# design.net
KiCad netlist of a schematic drawn in Altium Designer
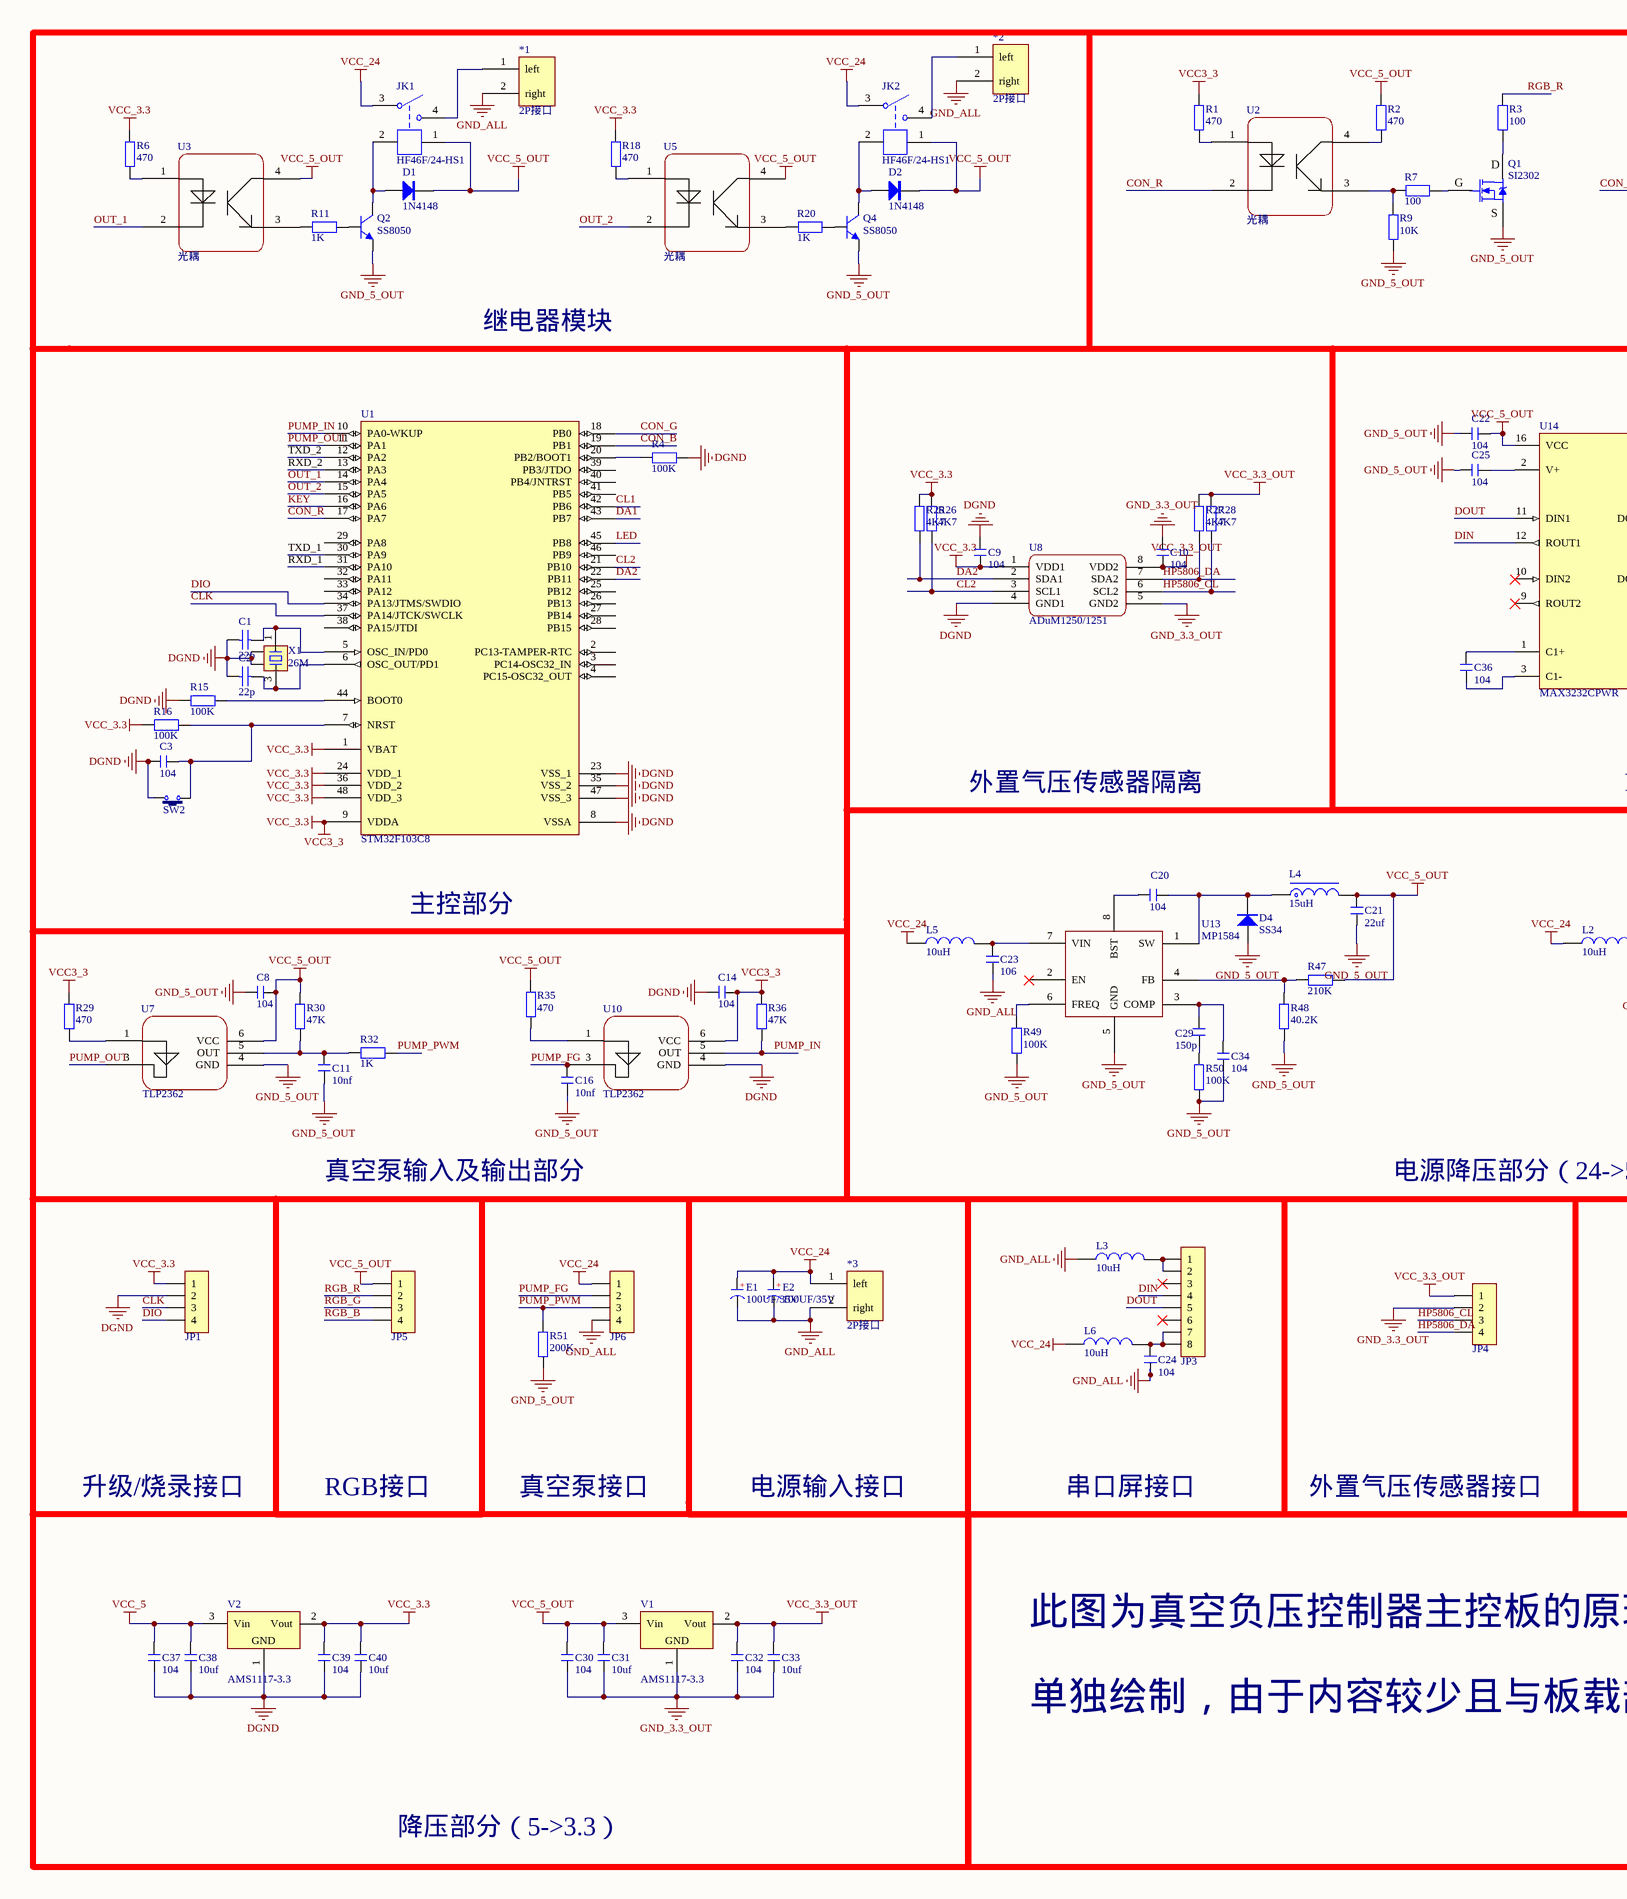
[diagram p0: 气压检测.SchDoc, left]
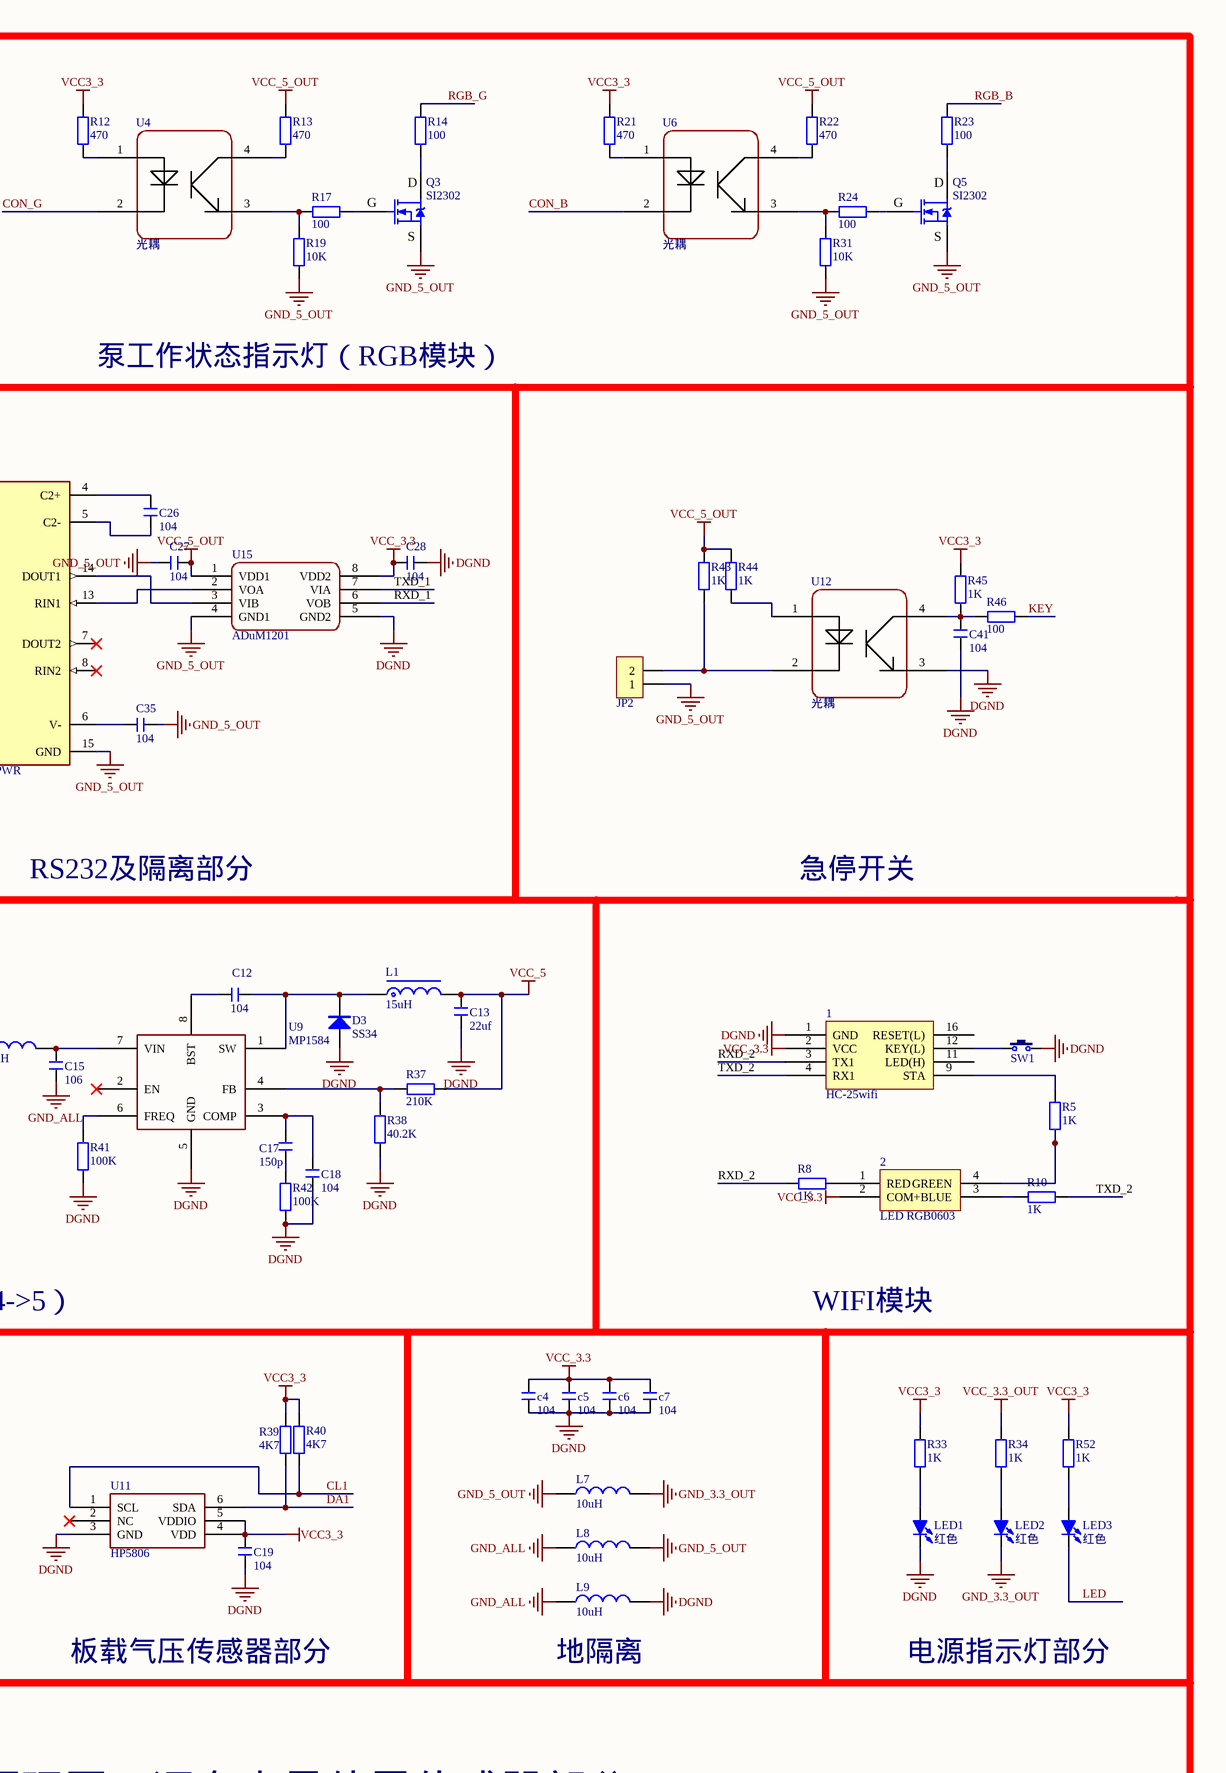
[diagram p1: 气压检测.SchDoc, right]

(export (version "E")
  (design (tool "Eeschema 10.0.6"))
  (components
    (comp (ref "*1") (value "2P接口") (footprint "KF128_2P") (libsource (lib "接口") (part "2P接口")))
    (comp (ref "*2") (value "2P接口") (footprint "KF128_2P") (libsource (lib "接口") (part "2P接口")))
    (comp (ref "*3") (value "2P接口") (footprint "KF128_2P") (libsource (lib "接口") (part "2P接口")))
    (comp (ref "1")
      (value "HC-25wifi")
      (footprint "HC-25")
      (description "HC-25WIFI无线模块")
      (libsource (lib "元件库") (part "HC-25wifi"))
    )
    (comp (ref "2")
      (value "LED RGB0603")
      (footprint "LED RGB 0603")
      (libsource (lib "二极管、LED") (part "LED RGB0603"))
    )
    (comp (ref "C1") (value "22p") (footprint "0603-cap") (libsource (lib "器件库") (part "Cap1")))
    (comp (ref "C2") (value "22p") (footprint "0603-cap") (libsource (lib "器件库") (part "Cap1")))
    (comp (ref "C3")
      (value "104")
      (footprint "C 0603_L")
      (description "无极性贴片电容")
      (fields (field (name "版权归属") "源创客"))
      (libsource (lib "电容、电阻、电感") (part "C"))
    )
    (comp (ref "c4")
      (value "104")
      (footprint "C 0603_L")
      (description "无极性贴片电容")
      (fields (field (name "版权归属") "源创客"))
      (libsource (lib "电容、电阻、电感") (part "C"))
    )
    (comp (ref "c5")
      (value "104")
      (footprint "C 0603_L")
      (description "无极性贴片电容")
      (fields (field (name "版权归属") "源创客"))
      (libsource (lib "电容、电阻、电感") (part "C"))
    )
    (comp (ref "c6")
      (value "104")
      (footprint "C 0603_L")
      (description "无极性贴片电容")
      (fields (field (name "版权归属") "源创客"))
      (libsource (lib "电容、电阻、电感") (part "C"))
    )
    (comp (ref "c7")
      (value "104")
      (footprint "C 0603_L")
      (description "无极性贴片电容")
      (fields (field (name "版权归属") "源创客"))
      (libsource (lib "电容、电阻、电感") (part "C"))
    )
    (comp (ref "C8")
      (value "104")
      (footprint "C 0603_L")
      (description "无极性贴片电容")
      (fields (field (name "版权归属") "源创客"))
      (libsource (lib "电容、电阻、电感") (part "C"))
    )
    (comp (ref "C9")
      (value "104")
      (footprint "C 0603_L")
      (description "无极性贴片电容")
      (fields (field (name "版权归属") "源创客"))
      (libsource (lib "电容、电阻、电感") (part "C"))
    )
    (comp (ref "C10")
      (value "104")
      (footprint "C 0603_L")
      (description "无极性贴片电容")
      (fields (field (name "版权归属") "源创客"))
      (libsource (lib "电容、电阻、电感") (part "C"))
    )
    (comp (ref "C11")
      (value "10nf")
      (footprint "C 0603_L")
      (description "无极性贴片电容")
      (fields (field (name "版权归属") "源创客"))
      (libsource (lib "电容、电阻、电感") (part "C"))
    )
    (comp (ref "C12")
      (value "104")
      (footprint "C 0603_L")
      (description "无极性贴片电容")
      (fields (field (name "版权归属") "源创客"))
      (libsource (lib "电容、电阻、电感") (part "C"))
    )
    (comp (ref "C13")
      (value "22uf")
      (footprint "C 1210_L")
      (description "无极性贴片电容")
      (fields (field (name "版权归属") "源创客"))
      (libsource (lib "电容、电阻、电感") (part "C"))
    )
    (comp (ref "C14")
      (value "104")
      (footprint "C 0603_L")
      (description "无极性贴片电容")
      (fields (field (name "版权归属") "源创客"))
      (libsource (lib "电容、电阻、电感") (part "C"))
    )
    (comp (ref "C15")
      (value "106")
      (footprint "C 1206_L")
      (description "无极性贴片电容")
      (fields (field (name "版权归属") "源创客"))
      (libsource (lib "电容、电阻、电感") (part "C"))
    )
    (comp (ref "C16")
      (value "10nf")
      (footprint "C 0603_L")
      (description "无极性贴片电容")
      (fields (field (name "版权归属") "源创客"))
      (libsource (lib "电容、电阻、电感") (part "C"))
    )
    (comp (ref "C17")
      (value "150p")
      (footprint "C 0603_L")
      (description "无极性贴片电容")
      (fields (field (name "版权归属") "源创客"))
      (libsource (lib "电容、电阻、电感") (part "C"))
    )
    (comp (ref "C18")
      (value "104")
      (footprint "C 0603_L")
      (description "无极性贴片电容")
      (fields (field (name "版权归属") "源创客"))
      (libsource (lib "电容、电阻、电感") (part "C"))
    )
    (comp (ref "C19")
      (value "104")
      (footprint "C 0603_L")
      (description "无极性贴片电容")
      (fields (field (name "版权归属") "源创客"))
      (libsource (lib "电容、电阻、电感") (part "C"))
    )
    (comp (ref "C20")
      (value "104")
      (footprint "C 0603_L")
      (description "无极性贴片电容")
      (fields (field (name "版权归属") "源创客"))
      (libsource (lib "电容、电阻、电感") (part "C"))
    )
    (comp (ref "C21")
      (value "22uf")
      (footprint "C 1210_L")
      (description "无极性贴片电容")
      (fields (field (name "版权归属") "源创客"))
      (libsource (lib "电容、电阻、电感") (part "C"))
    )
    (comp (ref "C22")
      (value "104")
      (footprint "C 0603_L")
      (description "无极性贴片电容")
      (fields (field (name "版权归属") "源创客"))
      (libsource (lib "电容、电阻、电感") (part "C"))
    )
    (comp (ref "C23")
      (value "106")
      (footprint "C 1206_L")
      (description "无极性贴片电容")
      (fields (field (name "版权归属") "源创客"))
      (libsource (lib "电容、电阻、电感") (part "C"))
    )
    (comp (ref "C24")
      (value "104")
      (footprint "C 0603_L")
      (description "无极性贴片电容")
      (fields (field (name "版权归属") "源创客"))
      (libsource (lib "电容、电阻、电感") (part "C"))
    )
    (comp (ref "C25")
      (value "104")
      (footprint "C 0603_L")
      (description "无极性贴片电容")
      (fields (field (name "版权归属") "源创客"))
      (libsource (lib "电容、电阻、电感") (part "C"))
    )
    (comp (ref "C26")
      (value "104")
      (footprint "C 0603_L")
      (description "无极性贴片电容")
      (fields (field (name "版权归属") "源创客"))
      (libsource (lib "电容、电阻、电感") (part "C"))
    )
    (comp (ref "C27")
      (value "104")
      (footprint "C 0603_L")
      (description "无极性贴片电容")
      (fields (field (name "版权归属") "源创客"))
      (libsource (lib "电容、电阻、电感") (part "C"))
    )
    (comp (ref "C28")
      (value "104")
      (footprint "C 0603_L")
      (description "无极性贴片电容")
      (fields (field (name "版权归属") "源创客"))
      (libsource (lib "电容、电阻、电感") (part "C"))
    )
    (comp (ref "C29")
      (value "150p")
      (footprint "C 0603_L")
      (description "无极性贴片电容")
      (fields (field (name "版权归属") "源创客"))
      (libsource (lib "电容、电阻、电感") (part "C"))
    )
    (comp (ref "C30")
      (value "104")
      (footprint "C 0603_L")
      (description "无极性贴片电容")
      (fields (field (name "版权归属") "源创客"))
      (libsource (lib "电容、电阻、电感") (part "C"))
    )
    (comp (ref "C31")
      (value "10uf")
      (footprint "C 0805_L")
      (description "无极性贴片电容")
      (fields (field (name "版权归属") "源创客"))
      (libsource (lib "电容、电阻、电感") (part "C"))
    )
    (comp (ref "C32")
      (value "104")
      (footprint "C 0603_L")
      (description "无极性贴片电容")
      (fields (field (name "版权归属") "源创客"))
      (libsource (lib "电容、电阻、电感") (part "C"))
    )
    (comp (ref "C33")
      (value "10uf")
      (footprint "C 0805_L")
      (description "无极性贴片电容")
      (fields (field (name "版权归属") "源创客"))
      (libsource (lib "电容、电阻、电感") (part "C"))
    )
    (comp (ref "C34")
      (value "104")
      (footprint "C 0603_L")
      (description "无极性贴片电容")
      (fields (field (name "版权归属") "源创客"))
      (libsource (lib "电容、电阻、电感") (part "C"))
    )
    (comp (ref "C35")
      (value "104")
      (footprint "C 0603_L")
      (description "无极性贴片电容")
      (fields (field (name "版权归属") "源创客"))
      (libsource (lib "电容、电阻、电感") (part "C"))
    )
    (comp (ref "C36")
      (value "104")
      (footprint "C 0603_L")
      (description "无极性贴片电容")
      (fields (field (name "版权归属") "源创客"))
      (libsource (lib "电容、电阻、电感") (part "C"))
    )
    (comp (ref "C37")
      (value "104")
      (footprint "C 0603_L")
      (description "无极性贴片电容")
      (fields (field (name "版权归属") "源创客"))
      (libsource (lib "电容、电阻、电感") (part "C"))
    )
    (comp (ref "C38")
      (value "10uf")
      (footprint "C 0805_L")
      (description "无极性贴片电容")
      (fields (field (name "版权归属") "源创客"))
      (libsource (lib "电容、电阻、电感") (part "C"))
    )
    (comp (ref "C39")
      (value "104")
      (footprint "C 0603_L")
      (description "无极性贴片电容")
      (fields (field (name "版权归属") "源创客"))
      (libsource (lib "电容、电阻、电感") (part "C"))
    )
    (comp (ref "C40")
      (value "10uf")
      (footprint "C 0805_L")
      (description "无极性贴片电容")
      (fields (field (name "版权归属") "源创客"))
      (libsource (lib "电容、电阻、电感") (part "C"))
    )
    (comp (ref "C41")
      (value "104")
      (footprint "C 0603_L")
      (description "无极性贴片电容")
      (fields (field (name "版权归属") "源创客"))
      (libsource (lib "电容、电阻、电感") (part "C"))
    )
    (comp (ref "D1")
      (value "1N4148")
      (footprint "SOD-323")
      (description "高速开关二极管")
      (fields (field (name "版权归属") "源创客"))
      (libsource (lib "二极管、LED") (part "1N4148"))
    )
    (comp (ref "D2")
      (value "1N4148")
      (footprint "SOD-323")
      (description "高速开关二极管")
      (fields (field (name "版权归属") "源创客"))
      (libsource (lib "二极管、LED") (part "1N4148"))
    )
    (comp (ref "D3")
      (value "SS34")
      (footprint "SMA")
      (description "肖特基二极管")
      (fields (field (name "版权归属") "源创客"))
      (libsource (lib "二极管、LED") (part "SS210"))
    )
    (comp (ref "D4")
      (value "SS34")
      (footprint "SMA")
      (description "肖特基二极管")
      (fields (field (name "版权归属") "源创客"))
      (libsource (lib "二极管、LED") (part "SS210"))
    )
    (comp (ref "E1")
      (value "100UF/35V")
      (footprint "CAP 3.5*8*11.5")
      (description "直插电解电容")
      (fields (field (name "版权归属") "源创客"))
      (libsource (lib "电容、电阻、电感") (part "C-CAP"))
    )
    (comp (ref "E2")
      (value "100UF/35V")
      (footprint "CAP 3.5*8*11.5")
      (description "直插电解电容")
      (fields (field (name "版权归属") "源创客"))
      (libsource (lib "电容、电阻、电感") (part "C-CAP"))
    )
    (comp (ref "JK1")
      (value "HF46F/24-HS1")
      (footprint "HF46-xx-HS1")
      (description "24V一组常开")
      (fields (field (name "版权归属") "源创客"))
      (libsource (lib "继电器") (part "HF46F/24-HS1"))
    )
    (comp (ref "JK2")
      (value "HF46F/24-HS1")
      (footprint "HF46-xx-HS1")
      (description "24V一组常开")
      (fields (field (name "版权归属") "源创客"))
      (libsource (lib "继电器") (part "HF46F/24-HS1"))
    )
    (comp (ref "JP1")
      (value "HDR-1X4")
      (footprint "XH2.54-LI-4P")
      (description "4P接插件")
      (fields (field (name "版权归属") "源创客"))
      (libsource (lib "排针") (part "Header 4"))
    )
    (comp (ref "JP2")
      (value "HDR-1X2")
      (footprint "XH2.54-LI-2P")
      (description "2P接插件")
      (fields (field (name "版权归属") "源创客"))
      (libsource (lib "排针") (part "Header 2"))
    )
    (comp (ref "JP3")
      (value "HDR-1X8")
      (footprint "FPC2.0-8卧贴-带锁扣")
      (description "8P接插件")
      (fields (field (name "版权归属") "源创客"))
      (libsource (lib "排针") (part "Header 8"))
    )
    (comp (ref "JP4")
      (value "HDR-1X4")
      (footprint "XH2.54-LI-4P")
      (description "4P接插件")
      (fields (field (name "版权归属") "源创客"))
      (libsource (lib "排针") (part "Header 4"))
    )
    (comp (ref "JP5")
      (value "HDR-1X4")
      (footprint "XH2.54-LI-4P")
      (description "4P接插件")
      (fields (field (name "版权归属") "源创客"))
      (libsource (lib "排针") (part "Header 4"))
    )
    (comp (ref "JP6")
      (value "HDR-1X4")
      (footprint "XH2.54-LI-4P")
      (description "4P接插件")
      (fields (field (name "版权归属") "源创客"))
      (libsource (lib "排针") (part "Header 4"))
    )
    (comp (ref "L1")
      (value "15uH")
      (footprint "L 06030")
      (description "贴片功率电感")
      (fields (field (name "版权归属") "源创客"))
      (libsource (lib "电容、电阻、电感") (part "L-CD"))
    )
    (comp (ref "L2")
      (value "10uH")
      (footprint "L 1206")
      (description "小功率贴片电感")
      (fields (field (name "版权归属") "源创客"))
      (libsource (lib "电容、电阻、电感") (part "L"))
    )
    (comp (ref "L3")
      (value "10uH")
      (footprint "L 1206")
      (description "小功率贴片电感")
      (fields (field (name "版权归属") "源创客"))
      (libsource (lib "电容、电阻、电感") (part "L"))
    )
    (comp (ref "L4")
      (value "15uH")
      (footprint "L 06030")
      (description "贴片功率电感")
      (fields (field (name "版权归属") "源创客"))
      (libsource (lib "电容、电阻、电感") (part "L-CD"))
    )
    (comp (ref "L5")
      (value "10uH")
      (footprint "L 1206")
      (description "小功率贴片电感")
      (fields (field (name "版权归属") "源创客"))
      (libsource (lib "电容、电阻、电感") (part "L"))
    )
    (comp (ref "L6")
      (value "10uH")
      (footprint "L 1206")
      (description "小功率贴片电感")
      (fields (field (name "版权归属") "源创客"))
      (libsource (lib "电容、电阻、电感") (part "L"))
    )
    (comp (ref "L7")
      (value "10uH")
      (footprint "L 1206")
      (description "小功率贴片电感")
      (fields (field (name "版权归属") "源创客"))
      (libsource (lib "电容、电阻、电感") (part "L"))
    )
    (comp (ref "L8")
      (value "10uH")
      (footprint "L 1206")
      (description "小功率贴片电感")
      (fields (field (name "版权归属") "源创客"))
      (libsource (lib "电容、电阻、电感") (part "L"))
    )
    (comp (ref "L9")
      (value "10uH")
      (footprint "L 1206")
      (description "小功率贴片电感")
      (fields (field (name "版权归属") "源创客"))
      (libsource (lib "电容、电阻、电感") (part "L"))
    )
    (comp (ref "LED1")
      (value "红色")
      (footprint "LED 0603R")
      (description "贴片LED")
      (fields (field (name "版权归属") "源创客"))
      (libsource (lib "二极管、LED") (part "LED-SMD"))
    )
    (comp (ref "LED2")
      (value "红色")
      (footprint "LED 0603R")
      (description "贴片LED")
      (fields (field (name "版权归属") "源创客"))
      (libsource (lib "二极管、LED") (part "LED-SMD"))
    )
    (comp (ref "LED3")
      (value "红色")
      (footprint "LED 0603R")
      (description "贴片LED")
      (fields (field (name "版权归属") "源创客"))
      (libsource (lib "二极管、LED") (part "LED-SMD"))
    )
    (comp (ref "Q1")
      (value "SI2302")
      (footprint "SOT23-3N")
      (description "N沟道场效应管")
      (fields (field (name "版权归属") "源创客"))
      (libsource (lib "场效应管、可控硅") (part "SI2302"))
    )
    (comp (ref "Q2")
      (value "SS8050")
      (footprint "SOT23-3N")
      (description "高频放大-NPN型")
      (fields (field (name "版权归属") "源创客"))
      (libsource (lib "三极管") (part "8050-SMD"))
    )
    (comp (ref "Q3")
      (value "SI2302")
      (footprint "SOT23-3N")
      (description "N沟道场效应管")
      (fields (field (name "版权归属") "源创客"))
      (libsource (lib "场效应管、可控硅") (part "SI2302"))
    )
    (comp (ref "Q4")
      (value "SS8050")
      (footprint "SOT23-3N")
      (description "高频放大-NPN型")
      (fields (field (name "版权归属") "源创客"))
      (libsource (lib "三极管") (part "8050-SMD"))
    )
    (comp (ref "Q5")
      (value "SI2302")
      (footprint "SOT23-3N")
      (description "N沟道场效应管")
      (fields (field (name "版权归属") "源创客"))
      (libsource (lib "场效应管、可控硅") (part "SI2302"))
    )
    (comp (ref "R1")
      (value "470")
      (footprint "R 0603_L")
      (description "贴片电阻")
      (fields (field (name "版权归属") "源创客"))
      (libsource (lib "电容、电阻、电感") (part "R"))
    )
    (comp (ref "R2")
      (value "470")
      (footprint "R 0603_L")
      (description "贴片电阻")
      (fields (field (name "版权归属") "源创客"))
      (libsource (lib "电容、电阻、电感") (part "R"))
    )
    (comp (ref "R3")
      (value "100")
      (footprint "R 1206_L")
      (description "贴片电阻")
      (fields (field (name "版权归属") "源创客"))
      (libsource (lib "电容、电阻、电感") (part "R"))
    )
    (comp (ref "R4")
      (value "100K")
      (footprint "R 0603_L")
      (description "贴片电阻")
      (fields (field (name "版权归属") "源创客"))
      (libsource (lib "电容、电阻、电感") (part "R"))
    )
    (comp (ref "R5")
      (value "1K")
      (footprint "R 0603_L")
      (description "贴片电阻")
      (fields (field (name "版权归属") "源创客"))
      (libsource (lib "电容、电阻、电感") (part "R"))
    )
    (comp (ref "R6")
      (value "470")
      (footprint "R 0603_L")
      (description "贴片电阻")
      (fields (field (name "版权归属") "源创客"))
      (libsource (lib "电容、电阻、电感") (part "R"))
    )
    (comp (ref "R7")
      (value "100")
      (footprint "R 0603_L")
      (description "贴片电阻")
      (fields (field (name "版权归属") "源创客"))
      (libsource (lib "电容、电阻、电感") (part "R"))
    )
    (comp (ref "R8")
      (value "1K")
      (footprint "R 0603_L")
      (description "贴片电阻")
      (fields (field (name "版权归属") "源创客"))
      (libsource (lib "电容、电阻、电感") (part "R"))
    )
    (comp (ref "R9")
      (value "10K")
      (footprint "R 0603_L")
      (description "贴片电阻")
      (fields (field (name "版权归属") "源创客"))
      (libsource (lib "电容、电阻、电感") (part "R"))
    )
    (comp (ref "R10")
      (value "1K")
      (footprint "R 0603_L")
      (description "贴片电阻")
      (fields (field (name "版权归属") "源创客"))
      (libsource (lib "电容、电阻、电感") (part "R"))
    )
    (comp (ref "R11")
      (value "1K")
      (footprint "R 0603_L")
      (description "贴片电阻")
      (fields (field (name "版权归属") "源创客"))
      (libsource (lib "电容、电阻、电感") (part "R"))
    )
    (comp (ref "R12")
      (value "470")
      (footprint "R 0603_L")
      (description "贴片电阻")
      (fields (field (name "版权归属") "源创客"))
      (libsource (lib "电容、电阻、电感") (part "R"))
    )
    (comp (ref "R13")
      (value "470")
      (footprint "R 0603_L")
      (description "贴片电阻")
      (fields (field (name "版权归属") "源创客"))
      (libsource (lib "电容、电阻、电感") (part "R"))
    )
    (comp (ref "R14")
      (value "100")
      (footprint "R 1206_L")
      (description "贴片电阻")
      (fields (field (name "版权归属") "源创客"))
      (libsource (lib "电容、电阻、电感") (part "R"))
    )
    (comp (ref "R15")
      (value "100K")
      (footprint "R 0603_L")
      (description "贴片电阻")
      (fields (field (name "版权归属") "源创客"))
      (libsource (lib "电容、电阻、电感") (part "R"))
    )
    (comp (ref "R16")
      (value "100K")
      (footprint "R 0603_L")
      (description "贴片电阻")
      (fields (field (name "版权归属") "源创客"))
      (libsource (lib "电容、电阻、电感") (part "R"))
    )
    (comp (ref "R17")
      (value "100")
      (footprint "R 0603_L")
      (description "贴片电阻")
      (fields (field (name "版权归属") "源创客"))
      (libsource (lib "电容、电阻、电感") (part "R"))
    )
    (comp (ref "R18")
      (value "470")
      (footprint "R 0603_L")
      (description "贴片电阻")
      (fields (field (name "版权归属") "源创客"))
      (libsource (lib "电容、电阻、电感") (part "R"))
    )
    (comp (ref "R19")
      (value "10K")
      (footprint "R 0603_L")
      (description "贴片电阻")
      (fields (field (name "版权归属") "源创客"))
      (libsource (lib "电容、电阻、电感") (part "R"))
    )
    (comp (ref "R20")
      (value "1K")
      (footprint "R 0603_L")
      (description "贴片电阻")
      (fields (field (name "版权归属") "源创客"))
      (libsource (lib "电容、电阻、电感") (part "R"))
    )
    (comp (ref "R21")
      (value "470")
      (footprint "R 0603_L")
      (description "贴片电阻")
      (fields (field (name "版权归属") "源创客"))
      (libsource (lib "电容、电阻、电感") (part "R"))
    )
    (comp (ref "R22")
      (value "470")
      (footprint "R 0603_L")
      (description "贴片电阻")
      (fields (field (name "版权归属") "源创客"))
      (libsource (lib "电容、电阻、电感") (part "R"))
    )
    (comp (ref "R23")
      (value "100")
      (footprint "R 1206_L")
      (description "贴片电阻")
      (fields (field (name "版权归属") "源创客"))
      (libsource (lib "电容、电阻、电感") (part "R"))
    )
    (comp (ref "R24")
      (value "100")
      (footprint "R 0603_L")
      (description "贴片电阻")
      (fields (field (name "版权归属") "源创客"))
      (libsource (lib "电容、电阻、电感") (part "R"))
    )
    (comp (ref "R25")
      (value "4K7")
      (footprint "R 0603_L")
      (description "贴片电阻")
      (fields (field (name "版权归属") "源创客"))
      (libsource (lib "电容、电阻、电感") (part "R"))
    )
    (comp (ref "R26")
      (value "4K7")
      (footprint "R 0603_L")
      (description "贴片电阻")
      (fields (field (name "版权归属") "源创客"))
      (libsource (lib "电容、电阻、电感") (part "R"))
    )
    (comp (ref "R27")
      (value "4K7")
      (footprint "R 0603_L")
      (description "贴片电阻")
      (fields (field (name "版权归属") "源创客"))
      (libsource (lib "电容、电阻、电感") (part "R"))
    )
    (comp (ref "R28")
      (value "4K7")
      (footprint "R 0603_L")
      (description "贴片电阻")
      (fields (field (name "版权归属") "源创客"))
      (libsource (lib "电容、电阻、电感") (part "R"))
    )
    (comp (ref "R29")
      (value "470")
      (footprint "R 0603_L")
      (description "贴片电阻")
      (fields (field (name "版权归属") "源创客"))
      (libsource (lib "电容、电阻、电感") (part "R"))
    )
    (comp (ref "R30")
      (value "47K")
      (footprint "R 0603_L")
      (description "贴片电阻")
      (fields (field (name "版权归属") "源创客"))
      (libsource (lib "电容、电阻、电感") (part "R"))
    )
    (comp (ref "R31")
      (value "10K")
      (footprint "R 0603_L")
      (description "贴片电阻")
      (fields (field (name "版权归属") "源创客"))
      (libsource (lib "电容、电阻、电感") (part "R"))
    )
    (comp (ref "R32")
      (value "1K")
      (footprint "R 0603_L")
      (description "贴片电阻")
      (fields (field (name "版权归属") "源创客"))
      (libsource (lib "电容、电阻、电感") (part "R"))
    )
    (comp (ref "R33")
      (value "1K")
      (footprint "R 0603_L")
      (description "贴片电阻")
      (fields (field (name "版权归属") "源创客"))
      (libsource (lib "电容、电阻、电感") (part "R"))
    )
    (comp (ref "R34")
      (value "1K")
      (footprint "R 0603_L")
      (description "贴片电阻")
      (fields (field (name "版权归属") "源创客"))
      (libsource (lib "电容、电阻、电感") (part "R"))
    )
    (comp (ref "R35")
      (value "470")
      (footprint "R 0603_L")
      (description "贴片电阻")
      (fields (field (name "版权归属") "源创客"))
      (libsource (lib "电容、电阻、电感") (part "R"))
    )
    (comp (ref "R36")
      (value "47K")
      (footprint "R 0603_L")
      (description "贴片电阻")
      (fields (field (name "版权归属") "源创客"))
      (libsource (lib "电容、电阻、电感") (part "R"))
    )
    (comp (ref "R37")
      (value "210K")
      (footprint "R 0603_L")
      (description "贴片电阻")
      (fields (field (name "版权归属") "源创客"))
      (libsource (lib "电容、电阻、电感") (part "R"))
    )
    (comp (ref "R38")
      (value "40.2K")
      (footprint "R 0603_L")
      (description "贴片电阻")
      (fields (field (name "版权归属") "源创客"))
      (libsource (lib "电容、电阻、电感") (part "R"))
    )
    (comp (ref "R39")
      (value "4K7")
      (footprint "R 0603_L")
      (description "贴片电阻")
      (fields (field (name "版权归属") "源创客"))
      (libsource (lib "电容、电阻、电感") (part "R"))
    )
    (comp (ref "R40")
      (value "4K7")
      (footprint "R 0603_L")
      (description "贴片电阻")
      (fields (field (name "版权归属") "源创客"))
      (libsource (lib "电容、电阻、电感") (part "R"))
    )
    (comp (ref "R41")
      (value "100K")
      (footprint "R 0603_L")
      (description "贴片电阻")
      (fields (field (name "版权归属") "源创客"))
      (libsource (lib "电容、电阻、电感") (part "R"))
    )
    (comp (ref "R42")
      (value "100K")
      (footprint "R 0603_L")
      (description "贴片电阻")
      (fields (field (name "版权归属") "源创客"))
      (libsource (lib "电容、电阻、电感") (part "R"))
    )
    (comp (ref "R43")
      (value "1K")
      (footprint "R 0603_L")
      (description "贴片电阻")
      (fields (field (name "版权归属") "源创客"))
      (libsource (lib "电容、电阻、电感") (part "R"))
    )
    (comp (ref "R44")
      (value "1K")
      (footprint "R 0603_L")
      (description "贴片电阻")
      (fields (field (name "版权归属") "源创客"))
      (libsource (lib "电容、电阻、电感") (part "R"))
    )
    (comp (ref "R45")
      (value "1K")
      (footprint "R 0603_L")
      (description "贴片电阻")
      (fields (field (name "版权归属") "源创客"))
      (libsource (lib "电容、电阻、电感") (part "R"))
    )
    (comp (ref "R46")
      (value "100")
      (footprint "R 0603_L")
      (description "贴片电阻")
      (fields (field (name "版权归属") "源创客"))
      (libsource (lib "电容、电阻、电感") (part "R"))
    )
    (comp (ref "R47")
      (value "210K")
      (footprint "R 0603_L")
      (description "贴片电阻")
      (fields (field (name "版权归属") "源创客"))
      (libsource (lib "电容、电阻、电感") (part "R"))
    )
    (comp (ref "R48")
      (value "40.2K")
      (footprint "R 0603_L")
      (description "贴片电阻")
      (fields (field (name "版权归属") "源创客"))
      (libsource (lib "电容、电阻、电感") (part "R"))
    )
    (comp (ref "R49")
      (value "100K")
      (footprint "R 0603_L")
      (description "贴片电阻")
      (fields (field (name "版权归属") "源创客"))
      (libsource (lib "电容、电阻、电感") (part "R"))
    )
    (comp (ref "R50")
      (value "100K")
      (footprint "R 0603_L")
      (description "贴片电阻")
      (fields (field (name "版权归属") "源创客"))
      (libsource (lib "电容、电阻、电感") (part "R"))
    )
    (comp (ref "R51")
      (value "200K")
      (footprint "R 0603_L")
      (description "贴片电阻")
      (fields (field (name "版权归属") "源创客"))
      (libsource (lib "电容、电阻、电感") (part "R"))
    )
    (comp (ref "R52")
      (value "1K")
      (footprint "R 0603_L")
      (description "贴片电阻")
      (fields (field (name "版权归属") "源创客"))
      (libsource (lib "电容、电阻、电感") (part "R"))
    )
    (comp (ref "SW1")
      (value "3x6x5")
      (footprint "TSW SMD-3*4*2")
      (description "3x6轻触开关")
      (fields (field (name "版权归属") "源创客"))
      (libsource (lib "") (part "TSW 3x6_1"))
    )
    (comp (ref "SW2")
      (value "3x6x5")
      (footprint "TSW SMD-3*4*2")
      (description "3x6轻触开关")
      (fields (field (name "版权归属") "源创客"))
      (libsource (lib "开关、按键") (part "TSW 3x6"))
    )
    (comp (ref "U1")
      (value "STM32F103C8")
      (footprint "LQFP48 7X7_N")
      (description "Flaah:64/RAM:20/IO:36")
      (fields (field (name "版权归属") "源创客"))
      (libsource (lib "STM32系列") (part "STM32F103C8"))
    )
    (comp (ref "U2")
      (value "光耦")
      (footprint "SMD-4")
      (description "低速单通道普通光耦")
      (libsource (lib "元件库") (part "光耦"))
    )
    (comp (ref "U3")
      (value "光耦")
      (footprint "SMD-4")
      (description "低速单通道普通光耦")
      (libsource (lib "元件库") (part "光耦"))
    )
    (comp (ref "U4")
      (value "光耦")
      (footprint "SMD-4")
      (description "低速单通道普通光耦")
      (libsource (lib "元件库") (part "光耦"))
    )
    (comp (ref "U5")
      (value "光耦")
      (footprint "SMD-4")
      (description "低速单通道普通光耦")
      (libsource (lib "元件库") (part "光耦"))
    )
    (comp (ref "U6")
      (value "光耦")
      (footprint "SMD-4")
      (description "低速单通道普通光耦")
      (libsource (lib "元件库") (part "光耦"))
    )
    (comp (ref "U7")
      (value "TLP2362")
      (footprint "SO6")
      (description "高速光耦（TOSHIBA)2.7-5.5V")
      (libsource (lib "元件库") (part "TLP2362"))
    )
    (comp (ref "U8")
      (value "ADuM1250/1251")
      (footprint "SOP8_L")
      (libsource (lib "芯片库") (part "ADuM1250/1251"))
    )
    (comp (ref "U9")
      (value "MP1584")
      (footprint "SOP8_N")
      (description "DC降压芯片")
      (libsource (lib "芯片库") (part "MP1584"))
    )
    (comp (ref "U10")
      (value "TLP2362")
      (footprint "SO6")
      (description "高速光耦（TOSHIBA)2.7-5.5V")
      (libsource (lib "元件库") (part "TLP2362"))
    )
    (comp (ref "U11")
      (value "HP5806")
      (footprint "HP5806")
      (description "I2C气压传感器")
      (libsource (lib "元件库") (part "HP5806"))
    )
    (comp (ref "U12")
      (value "光耦")
      (footprint "SMD-4")
      (description "低速单通道普通光耦")
      (libsource (lib "元件库") (part "光耦"))
    )
    (comp (ref "U13")
      (value "MP1584")
      (footprint "SOP8_N")
      (description "DC降压芯片")
      (libsource (lib "芯片库") (part "MP1584"))
    )
    (comp (ref "U14")
      (value "MAX3232CPWR")
      (footprint "FP-PW0016A-IPC_B")
      (description "IC TRANSCEIVER FULL 2/2 16TSSOP")
      (libsource (lib "Altium Content Vault") (part "35df3863a87d4fc5d5ee2311e0e958c"))
    )
    (comp (ref "U15")
      (value "ADuM1201")
      (footprint "SOP8_N")
      (description "通用隔离芯片")
      (libsource (lib "芯片库") (part "ADuM1201"))
    )
    (comp (ref "V1")
      (value "AMS1117-3.3")
      (footprint "SOT223_N")
      (description "三端稳压芯片")
      (fields (field (name "版权归属") "源创客"))
      (libsource (lib "电源类芯片") (part "AMS1117"))
    )
    (comp (ref "V2")
      (value "AMS1117-3.3")
      (footprint "SOT223_N")
      (description "三端稳压芯片")
      (fields (field (name "版权归属") "源创客"))
      (libsource (lib "电源类芯片") (part "AMS1117"))
    )
    (comp (ref "X1")
      (value "26M")
      (footprint "OSC 3225-4P")
      (description "4脚无源晶振")
      (fields (field (name "版权归属") "源创客"))
      (libsource (lib "晶振、保险丝") (part "XTAL-4P"))
    )
  )
  (nets
    (net (code "1") (name "/CL1") (class "Default")
      (node (ref "R40") (pin "2") (pinfunction "2_2") (pintype "passive"))
      (node (ref "U1") (pin "42") (pinfunction "PB6_42") (pintype "bidirectional"))
      (node (ref "U11") (pin "1") (pinfunction "SCL_1") (pintype "passive"))
    )
    (net (code "2") (name "/CL2") (class "Default")
      (node (ref "R26") (pin "1") (pinfunction "1_1") (pintype "passive"))
      (node (ref "U1") (pin "21") (pinfunction "PB10_21") (pintype "bidirectional"))
      (node (ref "U8") (pin "3") (pinfunction "SCL1_3") (pintype "passive"))
    )
    (net (code "3") (name "/CLK") (class "Default")
      (node (ref "JP1") (pin "3") (pinfunction "3_3") (pintype "passive"))
      (node (ref "U1") (pin "37") (pinfunction "PA14/JTCK/SWCLK_37") (pintype "bidirectional"))
    )
    (net (code "4") (name "/CON_B") (class "Default")
      (node (ref "U1") (pin "19") (pinfunction "PB1_19") (pintype "bidirectional"))
      (node (ref "U6") (pin "2") (pintype "passive"))
    )
    (net (code "5") (name "/CON_G") (class "Default")
      (node (ref "U1") (pin "18") (pinfunction "PB0_18") (pintype "bidirectional"))
      (node (ref "U4") (pin "2") (pintype "passive"))
    )
    (net (code "6") (name "/CON_R") (class "Default")
      (node (ref "U1") (pin "17") (pinfunction "PA7_17") (pintype "bidirectional"))
      (node (ref "U2") (pin "2") (pintype "passive"))
    )
    (net (code "7") (name "/DA1") (class "Default")
      (node (ref "R39") (pin "2") (pinfunction "2_2") (pintype "passive"))
      (node (ref "U1") (pin "43") (pinfunction "PB7_43") (pintype "bidirectional"))
      (node (ref "U11") (pin "6") (pinfunction "SDA_6") (pintype "passive"))
    )
    (net (code "8") (name "/DA2") (class "Default")
      (node (ref "R25") (pin "1") (pinfunction "1_1") (pintype "passive"))
      (node (ref "U1") (pin "22") (pinfunction "PB11_22") (pintype "bidirectional"))
      (node (ref "U8") (pin "2") (pinfunction "SDA1_2") (pintype "passive"))
    )
    (net (code "9") (name "/DIN") (class "Default")
      (node (ref "JP3") (pin "4") (pinfunction "4_4") (pintype "passive"))
      (node (ref "U14") (pin "12") (pinfunction "ROUT1_12") (pintype "output"))
    )
    (net (code "10") (name "/DIO") (class "Default")
      (node (ref "JP1") (pin "4") (pinfunction "4_4") (pintype "passive"))
      (node (ref "U1") (pin "34") (pinfunction "PA13/JTMS/SWDIO_34") (pintype "bidirectional"))
    )
    (net (code "11") (name "/DOUT") (class "Default")
      (node (ref "JP3") (pin "5") (pinfunction "5_5") (pintype "passive"))
      (node (ref "U14") (pin "11") (pinfunction "DIN1_11") (pintype "input"))
    )
    (net (code "12") (name "/HP5806_CL") (class "Default")
      (node (ref "JP4") (pin "3") (pinfunction "3_3") (pintype "passive"))
      (node (ref "R28") (pin "1") (pinfunction "1_1") (pintype "passive"))
      (node (ref "U8") (pin "6") (pinfunction "SCL2_6") (pintype "passive"))
    )
    (net (code "13") (name "/HP5806_DA") (class "Default")
      (node (ref "JP4") (pin "4") (pinfunction "4_4") (pintype "passive"))
      (node (ref "R27") (pin "1") (pinfunction "1_1") (pintype "passive"))
      (node (ref "U8") (pin "7") (pinfunction "SDA2_7") (pintype "passive"))
    )
    (net (code "14") (name "/KEY") (class "Default")
      (node (ref "R46") (pin "1") (pinfunction "1_1") (pintype "passive"))
      (node (ref "U1") (pin "16") (pinfunction "PA6_16") (pintype "bidirectional"))
    )
    (net (code "15") (name "/LED") (class "Default")
      (node (ref "LED3") (pin "2") (pinfunction "K_2") (pintype "passive"))
      (node (ref "U1") (pin "45") (pinfunction "PB8_45") (pintype "bidirectional"))
    )
    (net (code "16") (name "/OUT_1") (class "Default")
      (node (ref "U1") (pin "14") (pinfunction "PA4_14") (pintype "bidirectional"))
      (node (ref "U3") (pin "2") (pintype "passive"))
    )
    (net (code "17") (name "/OUT_2") (class "Default")
      (node (ref "U1") (pin "15") (pinfunction "PA5_15") (pintype "bidirectional"))
      (node (ref "U5") (pin "2") (pintype "passive"))
    )
    (net (code "18") (name "/PUMP_FG") (class "Default")
      (node (ref "C16") (pin "1") (pinfunction "1_1") (pintype "passive"))
      (node (ref "JP6") (pin "2") (pinfunction "2_2") (pintype "passive"))
      (node (ref "U10") (pin "3") (pintype "passive"))
    )
    (net (code "19") (name "/PUMP_IN") (class "Default")
      (node (ref "R36") (pin "1") (pinfunction "1_1") (pintype "passive"))
      (node (ref "U1") (pin "10") (pinfunction "PA0-WKUP_10") (pintype "bidirectional"))
      (node (ref "U10") (pin "5") (pinfunction "OUT_5") (pintype "passive"))
    )
    (net (code "20") (name "/PUMP_OUT") (class "Default")
      (node (ref "U1") (pin "11") (pinfunction "PA1_11") (pintype "bidirectional"))
      (node (ref "U7") (pin "3") (pintype "passive"))
    )
    (net (code "21") (name "/PUMP_PWM") (class "Default")
      (node (ref "JP6") (pin "3") (pinfunction "3_3") (pintype "passive"))
      (node (ref "R32") (pin "1") (pinfunction "1_1") (pintype "passive"))
      (node (ref "R51") (pin "2") (pinfunction "2_2") (pintype "passive"))
    )
    (net (code "22") (name "/RGB_B") (class "Default")
      (node (ref "JP5") (pin "4") (pinfunction "4_4") (pintype "passive"))
      (node (ref "R23") (pin "2") (pinfunction "2_2") (pintype "passive"))
    )
    (net (code "23") (name "/RGB_G") (class "Default")
      (node (ref "JP5") (pin "3") (pinfunction "3_3") (pintype "passive"))
      (node (ref "R14") (pin "2") (pinfunction "2_2") (pintype "passive"))
    )
    (net (code "24") (name "/RGB_R") (class "Default")
      (node (ref "JP5") (pin "2") (pinfunction "2_2") (pintype "passive"))
      (node (ref "R3") (pin "2") (pinfunction "2_2") (pintype "passive"))
    )
    (net (code "25") (name "/RXD_1") (class "Default")
      (node (ref "U1") (pin "31") (pinfunction "PA10_31") (pintype "bidirectional"))
      (node (ref "U15") (pin "6") (pinfunction "VOB_6") (pintype "passive"))
    )
    (net (code "26") (name "/RXD_2") (class "Default")
      (node (ref "1") (pin "3") (pinfunction "TX1_3") (pintype "passive"))
      (node (ref "R8") (pin "1") (pinfunction "1_1") (pintype "passive"))
      (node (ref "U1") (pin "13") (pinfunction "PA3_13") (pintype "bidirectional"))
    )
    (net (code "27") (name "/TXD_1") (class "Default")
      (node (ref "U1") (pin "30") (pinfunction "PA9_30") (pintype "bidirectional"))
      (node (ref "U15") (pin "7") (pinfunction "VIA_7") (pintype "passive"))
    )
    (net (code "28") (name "/TXD_2") (class "Default")
      (node (ref "1") (pin "4") (pinfunction "RX1_4") (pintype "passive"))
      (node (ref "R10") (pin "2") (pinfunction "2_2") (pintype "passive"))
      (node (ref "U1") (pin "12") (pinfunction "PA2_12") (pintype "bidirectional"))
    )
    (net (code "29") (name "DGND") (class "Default")
      (node (ref "1") (pin "1") (pinfunction "GND_1") (pintype "passive"))
      (node (ref "C1") (pin "2") (pinfunction "2_2") (pintype "passive"))
      (node (ref "C13") (pin "1") (pinfunction "1_1") (pintype "passive"))
      (node (ref "C14") (pin "2") (pinfunction "2_2") (pintype "passive"))
      (node (ref "C18") (pin "1") (pinfunction "1_1") (pintype "passive"))
      (node (ref "C19") (pin "2") (pinfunction "2_2") (pintype "passive"))
      (node (ref "C2") (pin "2") (pinfunction "2_2") (pintype "passive"))
      (node (ref "C28") (pin "2") (pinfunction "2_2") (pintype "passive"))
      (node (ref "C3") (pin "1") (pinfunction "1_1") (pintype "passive"))
      (node (ref "C37") (pin "1") (pinfunction "1_1") (pintype "passive"))
      (node (ref "C38") (pin "1") (pinfunction "1_1") (pintype "passive"))
      (node (ref "C39") (pin "1") (pinfunction "1_1") (pintype "passive"))
      (node (ref "C40") (pin "1") (pinfunction "1_1") (pintype "passive"))
      (node (ref "C41") (pin "2") (pinfunction "2_2") (pintype "passive"))
      (node (ref "C9") (pin "2") (pinfunction "2_2") (pintype "passive"))
      (node (ref "D3") (pin "1") (pinfunction "A_1") (pintype "passive"))
      (node (ref "JP1") (pin "2") (pinfunction "2_2") (pintype "passive"))
      (node (ref "L9") (pin "2") (pinfunction "2_2") (pintype "passive"))
      (node (ref "LED1") (pin "2") (pinfunction "K_2") (pintype "passive"))
      (node (ref "R15") (pin "1") (pinfunction "1_1") (pintype "passive"))
      (node (ref "R38") (pin "2") (pinfunction "2_2") (pintype "passive"))
      (node (ref "R4") (pin "1") (pinfunction "1_1") (pintype "passive"))
      (node (ref "R41") (pin "1") (pinfunction "1_1") (pintype "passive"))
      (node (ref "R42") (pin "2") (pinfunction "2_2") (pintype "passive"))
      (node (ref "SW1") (pin "2") (pinfunction "2_2") (pintype "passive"))
      (node (ref "SW2") (pin "2") (pinfunction "2_2") (pintype "passive"))
      (node (ref "U1") (pin "23") (pinfunction "VSS_1_23") (pintype "power_in"))
      (node (ref "U1") (pin "35") (pinfunction "VSS_2_35") (pintype "power_in"))
      (node (ref "U1") (pin "47") (pinfunction "VSS_3_47") (pintype "power_in"))
      (node (ref "U1") (pin "8") (pinfunction "VSSA_8") (pintype "power_in"))
      (node (ref "U10") (pin "4") (pinfunction "GND_4") (pintype "passive"))
      (node (ref "U11") (pin "3") (pinfunction "GND_3") (pintype "passive"))
      (node (ref "U12") (pin "3") (pintype "passive"))
      (node (ref "U15") (pin "5") (pinfunction "GND2_5") (pintype "passive"))
      (node (ref "U8") (pin "4") (pinfunction "GND1_4") (pintype "passive"))
      (node (ref "U9") (pin "5") (pinfunction "GND_5") (pintype "passive"))
      (node (ref "V2") (pin "1") (pinfunction "GND_1") (pintype "passive"))
      (node (ref "X1") (pin "2") (pinfunction "2_2") (pintype "passive"))
      (node (ref "X1") (pin "4") (pinfunction "4_4") (pintype "passive"))
      (node (ref "c4") (pin "1") (pinfunction "1_1") (pintype "passive"))
      (node (ref "c5") (pin "1") (pinfunction "1_1") (pintype "passive"))
      (node (ref "c6") (pin "1") (pinfunction "1_1") (pintype "passive"))
      (node (ref "c7") (pin "1") (pinfunction "1_1") (pintype "passive"))
    )
    (net (code "30") (name "GND_3.3_OUT") (class "Default")
      (node (ref "C10") (pin "2") (pinfunction "2_2") (pintype "passive"))
      (node (ref "C30") (pin "1") (pinfunction "1_1") (pintype "passive"))
      (node (ref "C31") (pin "1") (pinfunction "1_1") (pintype "passive"))
      (node (ref "C32") (pin "1") (pinfunction "1_1") (pintype "passive"))
      (node (ref "C33") (pin "1") (pinfunction "1_1") (pintype "passive"))
      (node (ref "JP4") (pin "2") (pinfunction "2_2") (pintype "passive"))
      (node (ref "L7") (pin "2") (pinfunction "2_2") (pintype "passive"))
      (node (ref "LED2") (pin "2") (pinfunction "K_2") (pintype "passive"))
      (node (ref "U8") (pin "5") (pinfunction "GND2_5") (pintype "passive"))
      (node (ref "V1") (pin "1") (pinfunction "GND_1") (pintype "passive"))
    )
    (net (code "31") (name "GND_5_OUT") (class "Default")
      (node (ref "C11") (pin "2") (pinfunction "2_2") (pintype "passive"))
      (node (ref "C16") (pin "2") (pinfunction "2_2") (pintype "passive"))
      (node (ref "C21") (pin "1") (pinfunction "1_1") (pintype "passive"))
      (node (ref "C22") (pin "2") (pinfunction "2_2") (pintype "passive"))
      (node (ref "C25") (pin "2") (pinfunction "2_2") (pintype "passive"))
      (node (ref "C27") (pin "2") (pinfunction "2_2") (pintype "passive"))
      (node (ref "C34") (pin "1") (pinfunction "1_1") (pintype "passive"))
      (node (ref "C35") (pin "2") (pinfunction "2_2") (pintype "passive"))
      (node (ref "C8") (pin "2") (pinfunction "2_2") (pintype "passive"))
      (node (ref "D4") (pin "1") (pinfunction "A_1") (pintype "passive"))
      (node (ref "JP2") (pin "1") (pinfunction "1_1") (pintype "passive"))
      (node (ref "L7") (pin "1") (pinfunction "1_1") (pintype "passive"))
      (node (ref "L8") (pin "2") (pinfunction "2_2") (pintype "passive"))
      (node (ref "Q1") (pin "2") (pinfunction "S_2") (pintype "passive"))
      (node (ref "Q2") (pin "2") (pinfunction "E_2") (pintype "passive"))
      (node (ref "Q3") (pin "2") (pinfunction "S_2") (pintype "passive"))
      (node (ref "Q4") (pin "2") (pinfunction "E_2") (pintype "passive"))
      (node (ref "Q5") (pin "2") (pinfunction "S_2") (pintype "passive"))
      (node (ref "R19") (pin "1") (pinfunction "1_1") (pintype "passive"))
      (node (ref "R31") (pin "1") (pinfunction "1_1") (pintype "passive"))
      (node (ref "R48") (pin "2") (pinfunction "2_2") (pintype "passive"))
      (node (ref "R49") (pin "1") (pinfunction "1_1") (pintype "passive"))
      (node (ref "R50") (pin "2") (pinfunction "2_2") (pintype "passive"))
      (node (ref "R51") (pin "1") (pinfunction "1_1") (pintype "passive"))
      (node (ref "R9") (pin "1") (pinfunction "1_1") (pintype "passive"))
      (node (ref "U13") (pin "5") (pinfunction "GND_5") (pintype "passive"))
      (node (ref "U14") (pin "15") (pinfunction "GND_15") (pintype "power_in"))
      (node (ref "U15") (pin "4") (pinfunction "GND1_4") (pintype "passive"))
      (node (ref "U7") (pin "4") (pinfunction "GND_4") (pintype "passive"))
    )
    (net (code "32") (name "GND_ALL") (class "Default")
      (node (ref "*1") (pin "2") (pinfunction "right_2") (pintype "passive"))
      (node (ref "*2") (pin "2") (pinfunction "right_2") (pintype "passive"))
      (node (ref "*3") (pin "2") (pinfunction "right_2") (pintype "passive"))
      (node (ref "C15") (pin "1") (pinfunction "1_1") (pintype "passive"))
      (node (ref "C23") (pin "1") (pinfunction "1_1") (pintype "passive"))
      (node (ref "C24") (pin "2") (pinfunction "2_2") (pintype "passive"))
      (node (ref "E1") (pin "2") (pinfunction "K_2") (pintype "passive"))
      (node (ref "E2") (pin "2") (pinfunction "K_2") (pintype "passive"))
      (node (ref "JP6") (pin "4") (pinfunction "4_4") (pintype "passive"))
      (node (ref "L3") (pin "1") (pinfunction "1_1") (pintype "passive"))
      (node (ref "L8") (pin "1") (pinfunction "1_1") (pintype "passive"))
      (node (ref "L9") (pin "1") (pinfunction "1_1") (pintype "passive"))
    )
    (net (code "33") (name "Net-(*1-left)") (class "Default")
      (node (ref "*1") (pin "1") (pinfunction "left_1") (pintype "passive"))
      (node (ref "JK1") (pin "4") (pinfunction "4_4") (pintype "passive"))
    )
    (net (code "34") (name "Net-(*2-left)") (class "Default")
      (node (ref "*2") (pin "1") (pinfunction "left_1") (pintype "passive"))
      (node (ref "JK2") (pin "4") (pinfunction "4_4") (pintype "passive"))
    )
    (net (code "35") (name "Net-(1-KEY(L))") (class "Default")
      (node (ref "1") (pin "12") (pinfunction "KEY(L)_12") (pintype "passive"))
      (node (ref "SW1") (pin "1") (pinfunction "1_1") (pintype "passive"))
    )
    (net (code "36") (name "Net-(1-STA)") (class "Default")
      (node (ref "1") (pin "9") (pinfunction "STA_9") (pintype "passive"))
      (node (ref "R5") (pin "1") (pinfunction "1_1") (pintype "passive"))
    )
    (net (code "37") (name "Net-(2-BLUE)") (class "Default")
      (node (ref "2") (pin "3") (pinfunction "BLUE_3") (pintype "passive"))
      (node (ref "R10") (pin "1") (pinfunction "1_1") (pintype "passive"))
    )
    (net (code "38") (name "Net-(2-GREEN)") (class "Default")
      (node (ref "2") (pin "4") (pinfunction "GREEN_4") (pintype "passive"))
      (node (ref "R5") (pin "2") (pinfunction "2_2") (pintype "passive"))
    )
    (net (code "39") (name "Net-(2-RED)") (class "Default")
      (node (ref "2") (pin "1") (pinfunction "RED_1") (pintype "passive"))
      (node (ref "R8") (pin "2") (pinfunction "2_2") (pintype "passive"))
    )
    (net (code "40") (name "Net-(C17-Pad1)") (class "Default")
      (node (ref "C17") (pin "1") (pinfunction "1_1") (pintype "passive"))
      (node (ref "R42") (pin "1") (pinfunction "1_1") (pintype "passive"))
    )
    (net (code "41") (name "Net-(C24-Pad1)") (class "Default")
      (node (ref "C24") (pin "1") (pinfunction "1_1") (pintype "passive"))
      (node (ref "JP3") (pin "7") (pinfunction "7_7") (pintype "passive"))
      (node (ref "JP3") (pin "8") (pinfunction "8_8") (pintype "passive"))
      (node (ref "L6") (pin "2") (pinfunction "2_2") (pintype "passive"))
    )
    (net (code "42") (name "Net-(C29-Pad1)") (class "Default")
      (node (ref "C29") (pin "1") (pinfunction "1_1") (pintype "passive"))
      (node (ref "R50") (pin "1") (pinfunction "1_1") (pintype "passive"))
    )
    (net (code "43") (name "Net-(C41-Pad1)") (class "Default")
      (node (ref "C41") (pin "1") (pinfunction "1_1") (pintype "passive"))
      (node (ref "R45") (pin "1") (pinfunction "1_1") (pintype "passive"))
      (node (ref "R46") (pin "2") (pinfunction "2_2") (pintype "passive"))
      (node (ref "U12") (pin "4") (pintype "passive"))
    )
    (net (code "44") (name "Net-(D1-A)") (class "Default")
      (node (ref "D1") (pin "1") (pinfunction "A_1") (pintype "passive"))
      (node (ref "JK1") (pin "2") (pinfunction "2_2") (pintype "passive"))
      (node (ref "Q2") (pin "3") (pinfunction "C_3") (pintype "passive"))
    )
    (net (code "45") (name "Net-(D2-A)") (class "Default")
      (node (ref "D2") (pin "1") (pinfunction "A_1") (pintype "passive"))
      (node (ref "JK2") (pin "2") (pinfunction "2_2") (pintype "passive"))
      (node (ref "Q4") (pin "3") (pinfunction "C_3") (pintype "passive"))
    )
    (net (code "46") (name "Net-(D3-K)") (class "Default")
      (node (ref "C12") (pin "1") (pinfunction "1_1") (pintype "passive"))
      (node (ref "D3") (pin "2") (pinfunction "K_2") (pintype "passive"))
      (node (ref "L1") (pin "1") (pinfunction "1_1") (pintype "passive"))
      (node (ref "U9") (pin "1") (pinfunction "SW_1") (pintype "passive"))
    )
    (net (code "47") (name "Net-(D4-K)") (class "Default")
      (node (ref "C20") (pin "1") (pinfunction "1_1") (pintype "passive"))
      (node (ref "D4") (pin "2") (pinfunction "K_2") (pintype "passive"))
      (node (ref "L4") (pin "1") (pinfunction "1_1") (pintype "passive"))
      (node (ref "U13") (pin "1") (pinfunction "SW_1") (pintype "passive"))
    )
    (net (code "48") (name "Net-(JP2-Pad2)") (class "Default")
      (node (ref "JP2") (pin "2") (pinfunction "2_2") (pintype "passive"))
      (node (ref "R43") (pin "1") (pinfunction "1_1") (pintype "passive"))
      (node (ref "U12") (pin "2") (pintype "passive"))
    )
    (net (code "49") (name "Net-(JP3-Pad1)") (class "Default")
      (node (ref "JP3") (pin "1") (pinfunction "1_1") (pintype "passive"))
      (node (ref "JP3") (pin "2") (pinfunction "2_2") (pintype "passive"))
      (node (ref "L3") (pin "2") (pinfunction "2_2") (pintype "passive"))
    )
    (net (code "50") (name "Net-(LED1-A)") (class "Default")
      (node (ref "LED1") (pin "1") (pinfunction "A_1") (pintype "passive"))
      (node (ref "R33") (pin "2") (pinfunction "2_2") (pintype "passive"))
    )
    (net (code "51") (name "Net-(LED2-A)") (class "Default")
      (node (ref "LED2") (pin "1") (pinfunction "A_1") (pintype "passive"))
      (node (ref "R34") (pin "2") (pinfunction "2_2") (pintype "passive"))
    )
    (net (code "52") (name "Net-(LED3-A)") (class "Default")
      (node (ref "LED3") (pin "1") (pinfunction "A_1") (pintype "passive"))
      (node (ref "R52") (pin "2") (pinfunction "2_2") (pintype "passive"))
    )
    (net (code "53") (name "Net-(Q1-D)") (class "Default")
      (node (ref "Q1") (pin "3") (pinfunction "D_3") (pintype "passive"))
      (node (ref "R3") (pin "1") (pinfunction "1_1") (pintype "passive"))
    )
    (net (code "54") (name "Net-(Q1-G)") (class "Default")
      (node (ref "Q1") (pin "1") (pinfunction "G_1") (pintype "passive"))
      (node (ref "R7") (pin "1") (pinfunction "1_1") (pintype "passive"))
    )
    (net (code "55") (name "Net-(Q2-B)") (class "Default")
      (node (ref "Q2") (pin "1") (pinfunction "B_1") (pintype "passive"))
      (node (ref "R11") (pin "2") (pinfunction "2_2") (pintype "passive"))
    )
    (net (code "56") (name "Net-(Q3-D)") (class "Default")
      (node (ref "Q3") (pin "3") (pinfunction "D_3") (pintype "passive"))
      (node (ref "R14") (pin "1") (pinfunction "1_1") (pintype "passive"))
    )
    (net (code "57") (name "Net-(Q3-G)") (class "Default")
      (node (ref "Q3") (pin "1") (pinfunction "G_1") (pintype "passive"))
      (node (ref "R17") (pin "1") (pinfunction "1_1") (pintype "passive"))
    )
    (net (code "58") (name "Net-(Q4-B)") (class "Default")
      (node (ref "Q4") (pin "1") (pinfunction "B_1") (pintype "passive"))
      (node (ref "R20") (pin "2") (pinfunction "2_2") (pintype "passive"))
    )
    (net (code "59") (name "Net-(Q5-D)") (class "Default")
      (node (ref "Q5") (pin "3") (pinfunction "D_3") (pintype "passive"))
      (node (ref "R23") (pin "1") (pinfunction "1_1") (pintype "passive"))
    )
    (net (code "60") (name "Net-(Q5-G)") (class "Default")
      (node (ref "Q5") (pin "1") (pinfunction "G_1") (pintype "passive"))
      (node (ref "R24") (pin "1") (pinfunction "1_1") (pintype "passive"))
    )
    (net (code "61") (name "Net-(R1-Pad1)") (class "Default")
      (node (ref "R1") (pin "1") (pinfunction "1_1") (pintype "passive"))
      (node (ref "U2") (pin "1") (pintype "passive"))
    )
    (net (code "62") (name "Net-(R2-Pad1)") (class "Default")
      (node (ref "R2") (pin "1") (pinfunction "1_1") (pintype "passive"))
      (node (ref "U2") (pin "4") (pintype "passive"))
    )
    (net (code "63") (name "Net-(R6-Pad1)") (class "Default")
      (node (ref "R6") (pin "1") (pinfunction "1_1") (pintype "passive"))
      (node (ref "U3") (pin "1") (pintype "passive"))
    )
    (net (code "64") (name "Net-(R7-Pad2)") (class "Default")
      (node (ref "R7") (pin "2") (pinfunction "2_2") (pintype "passive"))
      (node (ref "R9") (pin "2") (pinfunction "2_2") (pintype "passive"))
      (node (ref "U2") (pin "3") (pintype "passive"))
    )
    (net (code "65") (name "Net-(R11-Pad1)") (class "Default")
      (node (ref "R11") (pin "1") (pinfunction "1_1") (pintype "passive"))
      (node (ref "U3") (pin "3") (pintype "passive"))
    )
    (net (code "66") (name "Net-(R12-Pad1)") (class "Default")
      (node (ref "R12") (pin "1") (pinfunction "1_1") (pintype "passive"))
      (node (ref "U4") (pin "1") (pintype "passive"))
    )
    (net (code "67") (name "Net-(R13-Pad1)") (class "Default")
      (node (ref "R13") (pin "1") (pinfunction "1_1") (pintype "passive"))
      (node (ref "U4") (pin "4") (pintype "passive"))
    )
    (net (code "68") (name "Net-(R17-Pad2)") (class "Default")
      (node (ref "R17") (pin "2") (pinfunction "2_2") (pintype "passive"))
      (node (ref "R19") (pin "2") (pinfunction "2_2") (pintype "passive"))
      (node (ref "U4") (pin "3") (pintype "passive"))
    )
    (net (code "69") (name "Net-(R18-Pad1)") (class "Default")
      (node (ref "R18") (pin "1") (pinfunction "1_1") (pintype "passive"))
      (node (ref "U5") (pin "1") (pintype "passive"))
    )
    (net (code "70") (name "Net-(R20-Pad1)") (class "Default")
      (node (ref "R20") (pin "1") (pinfunction "1_1") (pintype "passive"))
      (node (ref "U5") (pin "3") (pintype "passive"))
    )
    (net (code "71") (name "Net-(R21-Pad1)") (class "Default")
      (node (ref "R21") (pin "1") (pinfunction "1_1") (pintype "passive"))
      (node (ref "U6") (pin "1") (pintype "passive"))
    )
    (net (code "72") (name "Net-(R22-Pad1)") (class "Default")
      (node (ref "R22") (pin "1") (pinfunction "1_1") (pintype "passive"))
      (node (ref "U6") (pin "4") (pintype "passive"))
    )
    (net (code "73") (name "Net-(R24-Pad2)") (class "Default")
      (node (ref "R24") (pin "2") (pinfunction "2_2") (pintype "passive"))
      (node (ref "R31") (pin "2") (pinfunction "2_2") (pintype "passive"))
      (node (ref "U6") (pin "3") (pintype "passive"))
    )
    (net (code "74") (name "Net-(R29-Pad1)") (class "Default")
      (node (ref "R29") (pin "1") (pinfunction "1_1") (pintype "passive"))
      (node (ref "U7") (pin "1") (pintype "passive"))
    )
    (net (code "75") (name "Net-(R35-Pad1)") (class "Default")
      (node (ref "R35") (pin "1") (pinfunction "1_1") (pintype "passive"))
      (node (ref "U10") (pin "1") (pintype "passive"))
    )
    (net (code "76") (name "Net-(R44-Pad1)") (class "Default")
      (node (ref "R44") (pin "1") (pinfunction "1_1") (pintype "passive"))
      (node (ref "U12") (pin "1") (pintype "passive"))
    )
    (net (code "77") (name "Net-(U1-BOOT0)") (class "Default")
      (node (ref "R15") (pin "2") (pinfunction "2_2") (pintype "passive"))
      (node (ref "U1") (pin "44") (pinfunction "BOOT0_44") (pintype "input"))
    )
    (net (code "78") (name "Net-(U1-NRST)") (class "Default")
      (node (ref "C3") (pin "2") (pinfunction "2_2") (pintype "passive"))
      (node (ref "R16") (pin "2") (pinfunction "2_2") (pintype "passive"))
      (node (ref "SW2") (pin "1") (pinfunction "1_1") (pintype "passive"))
      (node (ref "U1") (pin "7") (pinfunction "NRST_7") (pintype "bidirectional"))
    )
    (net (code "79") (name "Net-(U1-OSC_IN{slash}PD0)") (class "Default")
      (node (ref "C1") (pin "1") (pinfunction "1_1") (pintype "passive"))
      (node (ref "U1") (pin "5") (pinfunction "OSC_IN/PD0_5") (pintype "input"))
      (node (ref "X1") (pin "1") (pinfunction "1_1") (pintype "passive"))
    )
    (net (code "80") (name "Net-(U1-OSC_OUT{slash}PD1)") (class "Default")
      (node (ref "C2") (pin "1") (pinfunction "1_1") (pintype "passive"))
      (node (ref "U1") (pin "6") (pinfunction "OSC_OUT/PD1_6") (pintype "output"))
      (node (ref "X1") (pin "3") (pinfunction "3_3") (pintype "passive"))
    )
    (net (code "81") (name "Net-(U1-PB2{slash}BOOT1)") (class "Default")
      (node (ref "R4") (pin "2") (pinfunction "2_2") (pintype "passive"))
      (node (ref "U1") (pin "20") (pinfunction "PB2/BOOT1_20") (pintype "bidirectional"))
    )
    (net (code "82") (name "Net-(U7-OUT)") (class "Default")
      (node (ref "C11") (pin "1") (pinfunction "1_1") (pintype "passive"))
      (node (ref "R30") (pin "1") (pinfunction "1_1") (pintype "passive"))
      (node (ref "R32") (pin "2") (pinfunction "2_2") (pintype "passive"))
      (node (ref "U7") (pin "5") (pinfunction "OUT_5") (pintype "passive"))
    )
    (net (code "83") (name "Net-(U9-BST)") (class "Default")
      (node (ref "C12") (pin "2") (pinfunction "2_2") (pintype "passive"))
      (node (ref "U9") (pin "8") (pinfunction "BST_8") (pintype "passive"))
    )
    (net (code "84") (name "Net-(U9-COMP)") (class "Default")
      (node (ref "C17") (pin "2") (pinfunction "2_2") (pintype "passive"))
      (node (ref "C18") (pin "2") (pinfunction "2_2") (pintype "passive"))
      (node (ref "U9") (pin "3") (pinfunction "COMP_3") (pintype "passive"))
    )
    (net (code "85") (name "Net-(U9-FB)") (class "Default")
      (node (ref "R37") (pin "1") (pinfunction "1_1") (pintype "passive"))
      (node (ref "R38") (pin "1") (pinfunction "1_1") (pintype "passive"))
      (node (ref "U9") (pin "4") (pinfunction "FB_4") (pintype "passive"))
    )
    (net (code "86") (name "Net-(U9-FREQ)") (class "Default")
      (node (ref "R41") (pin "2") (pinfunction "2_2") (pintype "passive"))
      (node (ref "U9") (pin "6") (pinfunction "FREQ_6") (pintype "passive"))
    )
    (net (code "87") (name "Net-(U9-VIN)") (class "Default")
      (node (ref "C15") (pin "2") (pinfunction "2_2") (pintype "passive"))
      (node (ref "L2") (pin "2") (pinfunction "2_2") (pintype "passive"))
      (node (ref "U9") (pin "7") (pinfunction "VIN_7") (pintype "passive"))
    )
    (net (code "88") (name "Net-(U13-BST)") (class "Default")
      (node (ref "C20") (pin "2") (pinfunction "2_2") (pintype "passive"))
      (node (ref "U13") (pin "8") (pinfunction "BST_8") (pintype "passive"))
    )
    (net (code "89") (name "Net-(U13-COMP)") (class "Default")
      (node (ref "C29") (pin "2") (pinfunction "2_2") (pintype "passive"))
      (node (ref "C34") (pin "2") (pinfunction "2_2") (pintype "passive"))
      (node (ref "U13") (pin "3") (pinfunction "COMP_3") (pintype "passive"))
    )
    (net (code "90") (name "Net-(U13-FB)") (class "Default")
      (node (ref "R47") (pin "1") (pinfunction "1_1") (pintype "passive"))
      (node (ref "R48") (pin "1") (pinfunction "1_1") (pintype "passive"))
      (node (ref "U13") (pin "4") (pinfunction "FB_4") (pintype "passive"))
    )
    (net (code "91") (name "Net-(U13-FREQ)") (class "Default")
      (node (ref "R49") (pin "2") (pinfunction "2_2") (pintype "passive"))
      (node (ref "U13") (pin "6") (pinfunction "FREQ_6") (pintype "passive"))
    )
    (net (code "92") (name "Net-(U13-VIN)") (class "Default")
      (node (ref "C23") (pin "2") (pinfunction "2_2") (pintype "passive"))
      (node (ref "L5") (pin "2") (pinfunction "2_2") (pintype "passive"))
      (node (ref "U13") (pin "7") (pinfunction "VIN_7") (pintype "passive"))
    )
    (net (code "93") (name "Net-(U14-C1+)") (class "Default")
      (node (ref "C36") (pin "1") (pinfunction "1_1") (pintype "passive"))
      (node (ref "U14") (pin "1") (pinfunction "C1+_1") (pintype "passive"))
    )
    (net (code "94") (name "Net-(U14-C1-)") (class "Default")
      (node (ref "C36") (pin "2") (pinfunction "2_2") (pintype "passive"))
      (node (ref "U14") (pin "3") (pinfunction "C1-_3") (pintype "passive"))
    )
    (net (code "95") (name "Net-(U14-C2+)") (class "Default")
      (node (ref "C26") (pin "1") (pinfunction "1_1") (pintype "passive"))
      (node (ref "U14") (pin "4") (pinfunction "C2+_4") (pintype "passive"))
    )
    (net (code "96") (name "Net-(U14-C2-)") (class "Default")
      (node (ref "C26") (pin "2") (pinfunction "2_2") (pintype "passive"))
      (node (ref "U14") (pin "5") (pinfunction "C2-_5") (pintype "passive"))
    )
    (net (code "97") (name "Net-(U14-DOUT1)") (class "Default")
      (node (ref "U14") (pin "14") (pinfunction "DOUT1_14") (pintype "output"))
      (node (ref "U15") (pin "3") (pinfunction "VIB_3") (pintype "passive"))
    )
    (net (code "98") (name "Net-(U14-RIN1)") (class "Default")
      (node (ref "U14") (pin "13") (pinfunction "RIN1_13") (pintype "input"))
      (node (ref "U15") (pin "2") (pinfunction "VOA_2") (pintype "passive"))
    )
    (net (code "99") (name "Net-(U14-V+)") (class "Default")
      (node (ref "C25") (pin "1") (pinfunction "1_1") (pintype "passive"))
      (node (ref "U14") (pin "2") (pinfunction "V+_2") (pintype "power_in"))
    )
    (net (code "100") (name "Net-(U14-V-)") (class "Default")
      (node (ref "C35") (pin "1") (pinfunction "1_1") (pintype "passive"))
      (node (ref "U14") (pin "6") (pinfunction "V-_6") (pintype "power_in"))
    )
    (net (code "101") (name "VCC3_3") (class "Default")
      (node (ref "1") (pin "2") (pinfunction "VCC_2") (pintype "passive"))
      (node (ref "2") (pin "2") (pinfunction "COM+_2") (pintype "passive"))
      (node (ref "C14") (pin "1") (pinfunction "1_1") (pintype "passive"))
      (node (ref "C19") (pin "1") (pinfunction "1_1") (pintype "passive"))
      (node (ref "C28") (pin "1") (pinfunction "1_1") (pintype "passive"))
      (node (ref "C39") (pin "2") (pinfunction "2_2") (pintype "passive"))
      (node (ref "C40") (pin "2") (pinfunction "2_2") (pintype "passive"))
      (node (ref "C9") (pin "1") (pinfunction "1_1") (pintype "passive"))
      (node (ref "JP1") (pin "1") (pinfunction "1_1") (pintype "passive"))
      (node (ref "R1") (pin "2") (pinfunction "2_2") (pintype "passive"))
      (node (ref "R12") (pin "2") (pinfunction "2_2") (pintype "passive"))
      (node (ref "R16") (pin "1") (pinfunction "1_1") (pintype "passive"))
      (node (ref "R18") (pin "2") (pinfunction "2_2") (pintype "passive"))
      (node (ref "R21") (pin "2") (pinfunction "2_2") (pintype "passive"))
      (node (ref "R25") (pin "2") (pinfunction "2_2") (pintype "passive"))
      (node (ref "R26") (pin "2") (pinfunction "2_2") (pintype "passive"))
      (node (ref "R29") (pin "2") (pinfunction "2_2") (pintype "passive"))
      (node (ref "R33") (pin "1") (pinfunction "1_1") (pintype "passive"))
      (node (ref "R36") (pin "2") (pinfunction "2_2") (pintype "passive"))
      (node (ref "R39") (pin "1") (pinfunction "1_1") (pintype "passive"))
      (node (ref "R40") (pin "1") (pinfunction "1_1") (pintype "passive"))
      (node (ref "R45") (pin "2") (pinfunction "2_2") (pintype "passive"))
      (node (ref "R52") (pin "1") (pinfunction "1_1") (pintype "passive"))
      (node (ref "R6") (pin "2") (pinfunction "2_2") (pintype "passive"))
      (node (ref "U1") (pin "1") (pinfunction "VBAT_1") (pintype "power_in"))
      (node (ref "U1") (pin "24") (pinfunction "VDD_1_24") (pintype "power_in"))
      (node (ref "U1") (pin "36") (pinfunction "VDD_2_36") (pintype "power_in"))
      (node (ref "U1") (pin "48") (pinfunction "VDD_3_48") (pintype "power_in"))
      (node (ref "U1") (pin "9") (pinfunction "VDDA_9") (pintype "power_in"))
      (node (ref "U10") (pin "6") (pinfunction "VCC_6") (pintype "passive"))
      (node (ref "U11") (pin "4") (pinfunction "VDD_4") (pintype "passive"))
      (node (ref "U11") (pin "5") (pinfunction "VDDIO_5") (pintype "passive"))
      (node (ref "U15") (pin "8") (pinfunction "VDD2_8") (pintype "passive"))
      (node (ref "U8") (pin "1") (pinfunction "VDD1_1") (pintype "passive"))
      (node (ref "V2") (pin "2") (pinfunction "Vout_2") (pintype "passive"))
      (node (ref "c4") (pin "2") (pinfunction "2_2") (pintype "passive"))
      (node (ref "c5") (pin "2") (pinfunction "2_2") (pintype "passive"))
      (node (ref "c6") (pin "2") (pinfunction "2_2") (pintype "passive"))
      (node (ref "c7") (pin "2") (pinfunction "2_2") (pintype "passive"))
    )
    (net (code "102") (name "VCC_3.3_OUT") (class "Default")
      (node (ref "C10") (pin "1") (pinfunction "1_1") (pintype "passive"))
      (node (ref "C32") (pin "2") (pinfunction "2_2") (pintype "passive"))
      (node (ref "C33") (pin "2") (pinfunction "2_2") (pintype "passive"))
      (node (ref "JP4") (pin "1") (pinfunction "1_1") (pintype "passive"))
      (node (ref "R27") (pin "2") (pinfunction "2_2") (pintype "passive"))
      (node (ref "R28") (pin "2") (pinfunction "2_2") (pintype "passive"))
      (node (ref "R34") (pin "1") (pinfunction "1_1") (pintype "passive"))
      (node (ref "U8") (pin "8") (pinfunction "VDD2_8") (pintype "passive"))
      (node (ref "V1") (pin "2") (pinfunction "Vout_2") (pintype "passive"))
    )
    (net (code "103") (name "VCC_5") (class "Default")
      (node (ref "C13") (pin "2") (pinfunction "2_2") (pintype "passive"))
      (node (ref "C37") (pin "2") (pinfunction "2_2") (pintype "passive"))
      (node (ref "C38") (pin "2") (pinfunction "2_2") (pintype "passive"))
      (node (ref "L1") (pin "2") (pinfunction "2_2") (pintype "passive"))
      (node (ref "R37") (pin "2") (pinfunction "2_2") (pintype "passive"))
      (node (ref "V2") (pin "3") (pinfunction "Vin_3") (pintype "passive"))
    )
    (net (code "104") (name "VCC_5_OUT") (class "Default")
      (node (ref "C21") (pin "2") (pinfunction "2_2") (pintype "passive"))
      (node (ref "C22") (pin "1") (pinfunction "1_1") (pintype "passive"))
      (node (ref "C27") (pin "1") (pinfunction "1_1") (pintype "passive"))
      (node (ref "C30") (pin "2") (pinfunction "2_2") (pintype "passive"))
      (node (ref "C31") (pin "2") (pinfunction "2_2") (pintype "passive"))
      (node (ref "C8") (pin "1") (pinfunction "1_1") (pintype "passive"))
      (node (ref "D1") (pin "2") (pinfunction "K_2") (pintype "passive"))
      (node (ref "D2") (pin "2") (pinfunction "K_2") (pintype "passive"))
      (node (ref "JK1") (pin "1") (pinfunction "1_1") (pintype "passive"))
      (node (ref "JK2") (pin "1") (pinfunction "1_1") (pintype "passive"))
      (node (ref "JP5") (pin "1") (pinfunction "1_1") (pintype "passive"))
      (node (ref "L4") (pin "2") (pinfunction "2_2") (pintype "passive"))
      (node (ref "R13") (pin "2") (pinfunction "2_2") (pintype "passive"))
      (node (ref "R2") (pin "2") (pinfunction "2_2") (pintype "passive"))
      (node (ref "R22") (pin "2") (pinfunction "2_2") (pintype "passive"))
      (node (ref "R30") (pin "2") (pinfunction "2_2") (pintype "passive"))
      (node (ref "R35") (pin "2") (pinfunction "2_2") (pintype "passive"))
      (node (ref "R43") (pin "2") (pinfunction "2_2") (pintype "passive"))
      (node (ref "R44") (pin "2") (pinfunction "2_2") (pintype "passive"))
      (node (ref "R47") (pin "2") (pinfunction "2_2") (pintype "passive"))
      (node (ref "U14") (pin "16") (pinfunction "VCC_16") (pintype "power_in"))
      (node (ref "U15") (pin "1") (pinfunction "VDD1_1") (pintype "passive"))
      (node (ref "U3") (pin "4") (pintype "passive"))
      (node (ref "U5") (pin "4") (pintype "passive"))
      (node (ref "U7") (pin "6") (pinfunction "VCC_6") (pintype "passive"))
      (node (ref "V1") (pin "3") (pinfunction "Vin_3") (pintype "passive"))
    )
    (net (code "105") (name "VCC_24") (class "Default")
      (node (ref "*3") (pin "1") (pinfunction "left_1") (pintype "passive"))
      (node (ref "E1") (pin "1") (pinfunction "A_1") (pintype "passive"))
      (node (ref "E2") (pin "1") (pinfunction "A_1") (pintype "passive"))
      (node (ref "JK1") (pin "3") (pinfunction "3_3") (pintype "passive"))
      (node (ref "JK2") (pin "3") (pinfunction "3_3") (pintype "passive"))
      (node (ref "JP6") (pin "1") (pinfunction "1_1") (pintype "passive"))
      (node (ref "L2") (pin "1") (pinfunction "1_1") (pintype "passive"))
      (node (ref "L5") (pin "1") (pinfunction "1_1") (pintype "passive"))
      (node (ref "L6") (pin "1") (pinfunction "1_1") (pintype "passive"))
    )
    (net (code "106") (name "unconnected-(1-LED(H)-Pad11)") (class "Default")
      (node (ref "1") (pin "11") (pinfunction "LED(H)_11") (pintype "passive"))
    )
    (net (code "107") (name "unconnected-(1-RESET(L)-Pad16)") (class "Default")
      (node (ref "1") (pin "16") (pinfunction "RESET(L)_16") (pintype "passive"))
    )
    (net (code "108") (name "unconnected-(JP3-Pad3)") (class "Default")
      (node (ref "JP3") (pin "3") (pinfunction "3_3") (pintype "passive+no_connect"))
    )
    (net (code "109") (name "unconnected-(JP3-Pad6)") (class "Default")
      (node (ref "JP3") (pin "6") (pinfunction "6_6") (pintype "passive+no_connect"))
    )
    (net (code "110") (name "unconnected-(U1-PA8-Pad29)") (class "Default")
      (node (ref "U1") (pin "29") (pinfunction "PA8_29") (pintype "bidirectional"))
    )
    (net (code "111") (name "unconnected-(U1-PA11-Pad32)") (class "Default")
      (node (ref "U1") (pin "32") (pinfunction "PA11_32") (pintype "bidirectional"))
    )
    (net (code "112") (name "unconnected-(U1-PA12-Pad33)") (class "Default")
      (node (ref "U1") (pin "33") (pinfunction "PA12_33") (pintype "bidirectional"))
    )
    (net (code "113") (name "unconnected-(U1-PA15{slash}JTDI-Pad38)") (class "Default")
      (node (ref "U1") (pin "38") (pinfunction "PA15/JTDI_38") (pintype "bidirectional"))
    )
    (net (code "114") (name "unconnected-(U1-PB3{slash}JTDO-Pad39)") (class "Default")
      (node (ref "U1") (pin "39") (pinfunction "PB3/JTDO_39") (pintype "bidirectional"))
    )
    (net (code "115") (name "unconnected-(U1-PB4{slash}JNTRST-Pad40)") (class "Default")
      (node (ref "U1") (pin "40") (pinfunction "PB4/JNTRST_40") (pintype "bidirectional"))
    )
    (net (code "116") (name "unconnected-(U1-PB5-Pad41)") (class "Default")
      (node (ref "U1") (pin "41") (pinfunction "PB5_41") (pintype "bidirectional"))
    )
    (net (code "117") (name "unconnected-(U1-PB9-Pad46)") (class "Default")
      (node (ref "U1") (pin "46") (pinfunction "PB9_46") (pintype "bidirectional"))
    )
    (net (code "118") (name "unconnected-(U1-PB12-Pad25)") (class "Default")
      (node (ref "U1") (pin "25") (pinfunction "PB12_25") (pintype "bidirectional"))
    )
    (net (code "119") (name "unconnected-(U1-PB13-Pad26)") (class "Default")
      (node (ref "U1") (pin "26") (pinfunction "PB13_26") (pintype "bidirectional"))
    )
    (net (code "120") (name "unconnected-(U1-PB14-Pad27)") (class "Default")
      (node (ref "U1") (pin "27") (pinfunction "PB14_27") (pintype "bidirectional"))
    )
    (net (code "121") (name "unconnected-(U1-PB15-Pad28)") (class "Default")
      (node (ref "U1") (pin "28") (pinfunction "PB15_28") (pintype "bidirectional"))
    )
    (net (code "122") (name "unconnected-(U1-PC13-TAMPER-RTC-Pad2)") (class "Default")
      (node (ref "U1") (pin "2") (pinfunction "PC13-TAMPER-RTC_2") (pintype "bidirectional"))
    )
    (net (code "123") (name "unconnected-(U1-PC14-OSC32_IN-Pad3)") (class "Default")
      (node (ref "U1") (pin "3") (pinfunction "PC14-OSC32_IN_3") (pintype "bidirectional"))
    )
    (net (code "124") (name "unconnected-(U1-PC15-OSC32_OUT-Pad4)") (class "Default")
      (node (ref "U1") (pin "4") (pinfunction "PC15-OSC32_OUT_4") (pintype "bidirectional"))
    )
    (net (code "125") (name "unconnected-(U9-EN-Pad2)") (class "Default")
      (node (ref "U9") (pin "2") (pinfunction "EN_2") (pintype "passive+no_connect"))
    )
    (net (code "126") (name "unconnected-(U11-NC-Pad2)") (class "Default")
      (node (ref "U11") (pin "2") (pinfunction "NC_2") (pintype "passive+no_connect"))
    )
    (net (code "127") (name "unconnected-(U13-EN-Pad2)") (class "Default")
      (node (ref "U13") (pin "2") (pinfunction "EN_2") (pintype "passive+no_connect"))
    )
    (net (code "128") (name "unconnected-(U14-DIN2-Pad10)") (class "Default")
      (node (ref "U14") (pin "10") (pinfunction "DIN2_10") (pintype "input+no_connect"))
    )
    (net (code "129") (name "unconnected-(U14-DOUT2-Pad7)") (class "Default")
      (node (ref "U14") (pin "7") (pinfunction "DOUT2_7") (pintype "output+no_connect"))
    )
    (net (code "130") (name "unconnected-(U14-RIN2-Pad8)") (class "Default")
      (node (ref "U14") (pin "8") (pinfunction "RIN2_8") (pintype "input+no_connect"))
    )
    (net (code "131") (name "unconnected-(U14-ROUT2-Pad9)") (class "Default")
      (node (ref "U14") (pin "9") (pinfunction "ROUT2_9") (pintype "output+no_connect"))
    )
  )
)
